# pov.net
KiCad netlist of a schematic drawn in EAGLE
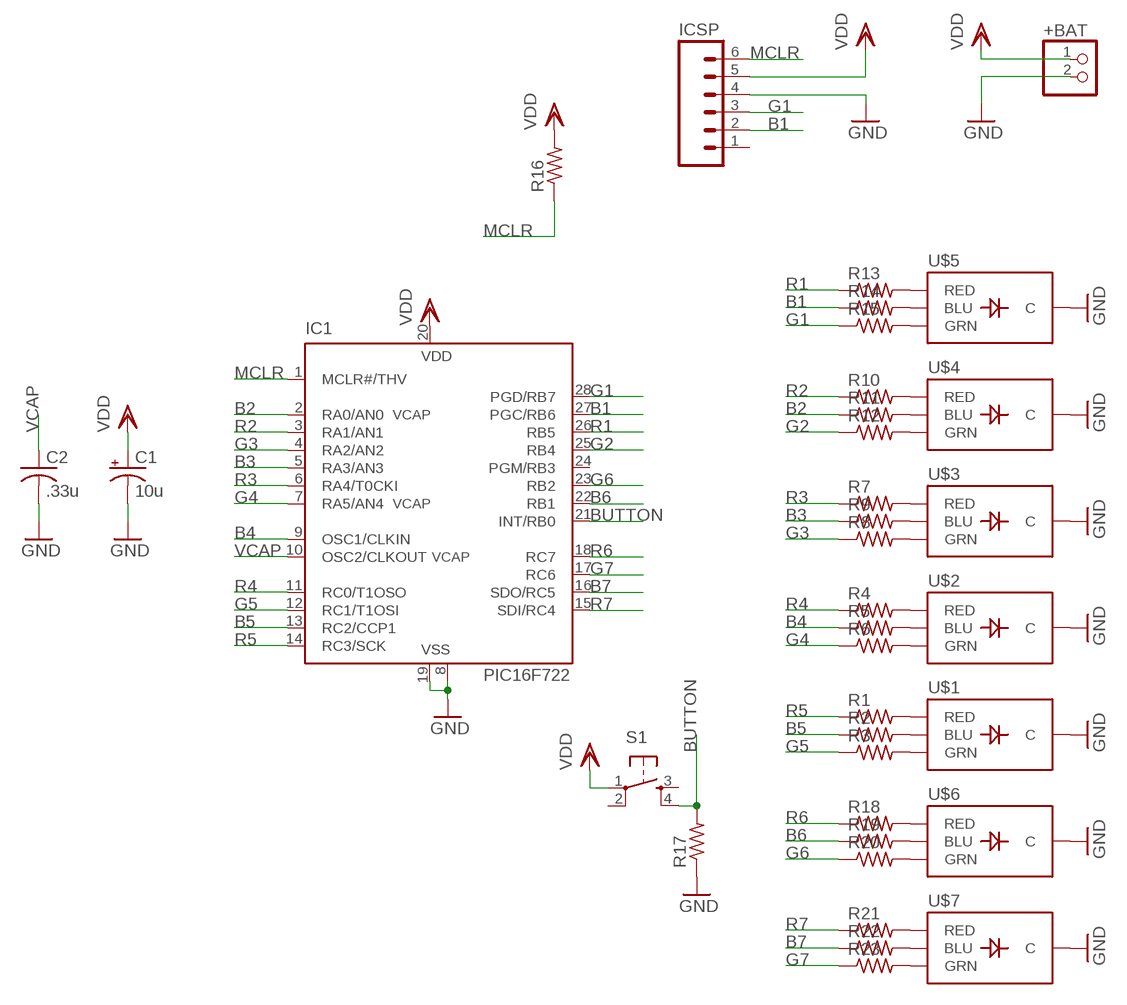
[diagram p0: schematic, sheet 1]

(export (version "E")
  (design (tool "Eeschema 10.0.6"))
  (components
    (comp (ref "+BAT")
      (value "PINHD-1X2")
      (footprint "eagle-import:1X02")
      (libsource (lib "eagle-import") (part "PINHD-1X2"))
    )
    (comp (ref "C1")
      (value "10u")
      (footprint "eagle-import:CPOL-RADIAL-10UF-25V")
      (libsource (lib "eagle-import") (part "CAP_POLPTH2"))
    )
    (comp (ref "C2")
      (value ".33u")
      (footprint "eagle-import:C050-024X044")
      (libsource (lib "eagle-import") (part "C-US050-024X044"))
    )
    (comp (ref "IC1")
      (value "PIC16F722")
      (footprint "eagle-import:DIL28-3")
      (libsource (lib "eagle-import") (part "PIC16872PF"))
    )
    (comp (ref "ICSP")
      (value "M06LOCK")
      (footprint "eagle-import:1X06_LOCK")
      (libsource (lib "eagle-import") (part "M06LOCK"))
    )
    (comp (ref "R1")
      (value "R-US_0207/10")
      (footprint "eagle-import:0207_10")
      (libsource (lib "eagle-import") (part "R-US_0207/10"))
    )
    (comp (ref "R2")
      (value "R-US_0207/10")
      (footprint "eagle-import:0207_10")
      (libsource (lib "eagle-import") (part "R-US_0207/10"))
    )
    (comp (ref "R3")
      (value "R-US_0207/10")
      (footprint "eagle-import:0207_10")
      (libsource (lib "eagle-import") (part "R-US_0207/10"))
    )
    (comp (ref "R4")
      (value "R-US_0207/10")
      (footprint "eagle-import:0207_10")
      (libsource (lib "eagle-import") (part "R-US_0207/10"))
    )
    (comp (ref "R5")
      (value "R-US_0207/10")
      (footprint "eagle-import:0207_10")
      (libsource (lib "eagle-import") (part "R-US_0207/10"))
    )
    (comp (ref "R6")
      (value "R-US_0207/10")
      (footprint "eagle-import:0207_10")
      (libsource (lib "eagle-import") (part "R-US_0207/10"))
    )
    (comp (ref "R7")
      (value "R-US_0207/10")
      (footprint "eagle-import:0207_10")
      (libsource (lib "eagle-import") (part "R-US_0207/10"))
    )
    (comp (ref "R8")
      (value "R-US_0207/10")
      (footprint "eagle-import:0207_10")
      (libsource (lib "eagle-import") (part "R-US_0207/10"))
    )
    (comp (ref "R9")
      (value "R-US_0207/10")
      (footprint "eagle-import:0207_10")
      (libsource (lib "eagle-import") (part "R-US_0207/10"))
    )
    (comp (ref "R10")
      (value "R-US_0207/10")
      (footprint "eagle-import:0207_10")
      (libsource (lib "eagle-import") (part "R-US_0207/10"))
    )
    (comp (ref "R11")
      (value "R-US_0207/10")
      (footprint "eagle-import:0207_10")
      (libsource (lib "eagle-import") (part "R-US_0207/10"))
    )
    (comp (ref "R12")
      (value "R-US_0207/10")
      (footprint "eagle-import:0207_10")
      (libsource (lib "eagle-import") (part "R-US_0207/10"))
    )
    (comp (ref "R13")
      (value "R-US_0207/10")
      (footprint "eagle-import:0207_10")
      (libsource (lib "eagle-import") (part "R-US_0207/10"))
    )
    (comp (ref "R14")
      (value "R-US_0207/10")
      (footprint "eagle-import:0207_10")
      (libsource (lib "eagle-import") (part "R-US_0207/10"))
    )
    (comp (ref "R15")
      (value "R-US_0207/10")
      (footprint "eagle-import:0207_10")
      (libsource (lib "eagle-import") (part "R-US_0207/10"))
    )
    (comp (ref "R16")
      (value "R-US_0207/10")
      (footprint "eagle-import:0207_10")
      (libsource (lib "eagle-import") (part "R-US_0207/10"))
    )
    (comp (ref "R17")
      (value "R-US_0207/10")
      (footprint "eagle-import:0207_10")
      (libsource (lib "eagle-import") (part "R-US_0207/10"))
    )
    (comp (ref "R18")
      (value "R-US_0207/10")
      (footprint "eagle-import:0207_10")
      (libsource (lib "eagle-import") (part "R-US_0207/10"))
    )
    (comp (ref "R19")
      (value "R-US_0207/10")
      (footprint "eagle-import:0207_10")
      (libsource (lib "eagle-import") (part "R-US_0207/10"))
    )
    (comp (ref "R20")
      (value "R-US_0207/10")
      (footprint "eagle-import:0207_10")
      (libsource (lib "eagle-import") (part "R-US_0207/10"))
    )
    (comp (ref "R21")
      (value "R-US_0207/10")
      (footprint "eagle-import:0207_10")
      (libsource (lib "eagle-import") (part "R-US_0207/10"))
    )
    (comp (ref "R22")
      (value "R-US_0207/10")
      (footprint "eagle-import:0207_10")
      (libsource (lib "eagle-import") (part "R-US_0207/10"))
    )
    (comp (ref "R23")
      (value "R-US_0207/10")
      (footprint "eagle-import:0207_10")
      (libsource (lib "eagle-import") (part "R-US_0207/10"))
    )
    (comp (ref "S1")
      (value "TAC_SWITCHPTH")
      (footprint "eagle-import:TACTILE-PTH")
      (libsource (lib "eagle-import") (part "TAC_SWITCHPTH"))
    )
    (comp (ref "U$1")
      (value "LED-TRICOLOR-THROUGHHOLE")
      (footprint "eagle-import:LED-TRICOLOR-THROUGHHOLE")
      (libsource (lib "eagle-import") (part "LED-TRICOLOR-THROUGHHOLE"))
    )
    (comp (ref "U$2")
      (value "LED-TRICOLOR-THROUGHHOLE")
      (footprint "eagle-import:LED-TRICOLOR-THROUGHHOLE")
      (libsource (lib "eagle-import") (part "LED-TRICOLOR-THROUGHHOLE"))
    )
    (comp (ref "U$3")
      (value "LED-TRICOLOR-THROUGHHOLE")
      (footprint "eagle-import:LED-TRICOLOR-THROUGHHOLE")
      (libsource (lib "eagle-import") (part "LED-TRICOLOR-THROUGHHOLE"))
    )
    (comp (ref "U$4")
      (value "LED-TRICOLOR-THROUGHHOLE")
      (footprint "eagle-import:LED-TRICOLOR-THROUGHHOLE")
      (libsource (lib "eagle-import") (part "LED-TRICOLOR-THROUGHHOLE"))
    )
    (comp (ref "U$5")
      (value "LED-TRICOLOR-THROUGHHOLE")
      (footprint "eagle-import:LED-TRICOLOR-THROUGHHOLE")
      (libsource (lib "eagle-import") (part "LED-TRICOLOR-THROUGHHOLE"))
    )
    (comp (ref "U$6")
      (value "LED-TRICOLOR-THROUGHHOLE")
      (footprint "eagle-import:LED-TRICOLOR-THROUGHHOLE")
      (libsource (lib "eagle-import") (part "LED-TRICOLOR-THROUGHHOLE"))
    )
    (comp (ref "U$7")
      (value "LED-TRICOLOR-THROUGHHOLE")
      (footprint "eagle-import:LED-TRICOLOR-THROUGHHOLE")
      (libsource (lib "eagle-import") (part "LED-TRICOLOR-THROUGHHOLE"))
    )
  )
  (nets
    (net (code "1") (name "/B1") (class "Default")
      (node (ref "IC1") (pin "27") (pinfunction "PGC/RB6_27") (pintype "bidirectional"))
      (node (ref "ICSP") (pin "2") (pinfunction "2_2") (pintype "passive"))
      (node (ref "R14") (pin "1") (pinfunction "1_1") (pintype "passive"))
    )
    (net (code "2") (name "/B2") (class "Default")
      (node (ref "IC1") (pin "2") (pinfunction "RA0/AN0_2") (pintype "bidirectional"))
      (node (ref "R11") (pin "1") (pinfunction "1_1") (pintype "passive"))
    )
    (net (code "3") (name "/B3") (class "Default")
      (node (ref "IC1") (pin "5") (pinfunction "RA3/AN3_5") (pintype "bidirectional"))
      (node (ref "R9") (pin "1") (pinfunction "1_1") (pintype "passive"))
    )
    (net (code "4") (name "/B4") (class "Default")
      (node (ref "IC1") (pin "9") (pinfunction "OSC1/CLKIN_9") (pintype "input"))
      (node (ref "R5") (pin "1") (pinfunction "1_1") (pintype "passive"))
    )
    (net (code "5") (name "/B5") (class "Default")
      (node (ref "IC1") (pin "13") (pinfunction "RC2/CCP1_13") (pintype "bidirectional"))
      (node (ref "R2") (pin "1") (pinfunction "1_1") (pintype "passive"))
    )
    (net (code "6") (name "/B6") (class "Default")
      (node (ref "IC1") (pin "22") (pinfunction "RB1_22") (pintype "bidirectional"))
      (node (ref "R19") (pin "1") (pinfunction "1_1") (pintype "passive"))
    )
    (net (code "7") (name "/B7") (class "Default")
      (node (ref "IC1") (pin "16") (pinfunction "SDO/RC5_16") (pintype "bidirectional"))
      (node (ref "R22") (pin "1") (pinfunction "1_1") (pintype "passive"))
    )
    (net (code "8") (name "/BUTTON") (class "Default")
      (node (ref "IC1") (pin "21") (pinfunction "INT/RB0_21") (pintype "bidirectional"))
      (node (ref "R17") (pin "2") (pinfunction "2_2") (pintype "passive"))
      (node (ref "S1") (pin "4") (pinfunction "4_4") (pintype "passive"))
    )
    (net (code "9") (name "/G1") (class "Default")
      (node (ref "IC1") (pin "28") (pinfunction "PGD/RB7_28") (pintype "bidirectional"))
      (node (ref "ICSP") (pin "3") (pinfunction "3_3") (pintype "passive"))
      (node (ref "R15") (pin "1") (pinfunction "1_1") (pintype "passive"))
    )
    (net (code "10") (name "/G2") (class "Default")
      (node (ref "IC1") (pin "25") (pinfunction "RB4_25") (pintype "bidirectional"))
      (node (ref "R12") (pin "1") (pinfunction "1_1") (pintype "passive"))
    )
    (net (code "11") (name "/G3") (class "Default")
      (node (ref "IC1") (pin "4") (pinfunction "RA2/AN2_4") (pintype "bidirectional"))
      (node (ref "R8") (pin "1") (pinfunction "1_1") (pintype "passive"))
    )
    (net (code "12") (name "/G4") (class "Default")
      (node (ref "IC1") (pin "7") (pinfunction "RA5/AN4_7") (pintype "bidirectional"))
      (node (ref "R6") (pin "1") (pinfunction "1_1") (pintype "passive"))
    )
    (net (code "13") (name "/G5") (class "Default")
      (node (ref "IC1") (pin "12") (pinfunction "RC1/T1OSI_12") (pintype "bidirectional"))
      (node (ref "R3") (pin "1") (pinfunction "1_1") (pintype "passive"))
    )
    (net (code "14") (name "/G6") (class "Default")
      (node (ref "IC1") (pin "23") (pinfunction "RB2_23") (pintype "bidirectional"))
      (node (ref "R20") (pin "1") (pinfunction "1_1") (pintype "passive"))
    )
    (net (code "15") (name "/G7") (class "Default")
      (node (ref "IC1") (pin "17") (pinfunction "RC6_17") (pintype "bidirectional"))
      (node (ref "R23") (pin "1") (pinfunction "1_1") (pintype "passive"))
    )
    (net (code "16") (name "/MCLR") (class "Default")
      (node (ref "IC1") (pin "1") (pinfunction "MCLR#/THV_1") (pintype "input"))
      (node (ref "ICSP") (pin "6") (pinfunction "6_6") (pintype "passive"))
      (node (ref "R16") (pin "1") (pinfunction "1_1") (pintype "passive"))
    )
    (net (code "17") (name "/R1") (class "Default")
      (node (ref "IC1") (pin "26") (pinfunction "RB5_26") (pintype "bidirectional"))
      (node (ref "R13") (pin "1") (pinfunction "1_1") (pintype "passive"))
    )
    (net (code "18") (name "/R2") (class "Default")
      (node (ref "IC1") (pin "3") (pinfunction "RA1/AN1_3") (pintype "bidirectional"))
      (node (ref "R10") (pin "1") (pinfunction "1_1") (pintype "passive"))
    )
    (net (code "19") (name "/R3") (class "Default")
      (node (ref "IC1") (pin "6") (pinfunction "RA4/T0CKI_6") (pintype "bidirectional"))
      (node (ref "R7") (pin "1") (pinfunction "1_1") (pintype "passive"))
    )
    (net (code "20") (name "/R4") (class "Default")
      (node (ref "IC1") (pin "11") (pinfunction "RC0/T1OSO_11") (pintype "bidirectional"))
      (node (ref "R4") (pin "1") (pinfunction "1_1") (pintype "passive"))
    )
    (net (code "21") (name "/R5") (class "Default")
      (node (ref "IC1") (pin "14") (pinfunction "RC3/SCK_14") (pintype "bidirectional"))
      (node (ref "R1") (pin "1") (pinfunction "1_1") (pintype "passive"))
    )
    (net (code "22") (name "/R6") (class "Default")
      (node (ref "IC1") (pin "18") (pinfunction "RC7_18") (pintype "bidirectional"))
      (node (ref "R18") (pin "1") (pinfunction "1_1") (pintype "passive"))
    )
    (net (code "23") (name "/R7") (class "Default")
      (node (ref "IC1") (pin "15") (pinfunction "SDI/RC4_15") (pintype "bidirectional"))
      (node (ref "R21") (pin "1") (pinfunction "1_1") (pintype "passive"))
    )
    (net (code "24") (name "/VCAP") (class "Default")
      (node (ref "C2") (pin "1") (pinfunction "1_1") (pintype "passive"))
      (node (ref "IC1") (pin "10") (pinfunction "OSC2/CLKOUT_10") (pintype "output"))
    )
    (net (code "25") (name "GND") (class "Default")
      (node (ref "+BAT") (pin "2") (pinfunction "2_2") (pintype "passive"))
      (node (ref "C1") (pin "2") (pinfunction "-_2") (pintype "passive"))
      (node (ref "C2") (pin "2") (pinfunction "2_2") (pintype "passive"))
      (node (ref "IC1") (pin "19") (pinfunction "VSS_19") (pintype "power_in"))
      (node (ref "IC1") (pin "8") (pinfunction "VSS_8") (pintype "power_in"))
      (node (ref "ICSP") (pin "4") (pinfunction "4_4") (pintype "passive"))
      (node (ref "R17") (pin "1") (pinfunction "1_1") (pintype "passive"))
      (node (ref "U$1") (pin "GND") (pinfunction "C_GND") (pintype "bidirectional"))
      (node (ref "U$2") (pin "GND") (pinfunction "C_GND") (pintype "bidirectional"))
      (node (ref "U$3") (pin "GND") (pinfunction "C_GND") (pintype "bidirectional"))
      (node (ref "U$4") (pin "GND") (pinfunction "C_GND") (pintype "bidirectional"))
      (node (ref "U$5") (pin "GND") (pinfunction "C_GND") (pintype "bidirectional"))
      (node (ref "U$6") (pin "GND") (pinfunction "C_GND") (pintype "bidirectional"))
      (node (ref "U$7") (pin "GND") (pinfunction "C_GND") (pintype "bidirectional"))
    )
    (net (code "26") (name "Net-(R1-Pad2)") (class "Default")
      (node (ref "R1") (pin "2") (pinfunction "2_2") (pintype "passive"))
      (node (ref "U$1") (pin "RED") (pinfunction "RED_RED") (pintype "bidirectional"))
    )
    (net (code "27") (name "Net-(R2-Pad2)") (class "Default")
      (node (ref "R2") (pin "2") (pinfunction "2_2") (pintype "passive"))
      (node (ref "U$1") (pin "BLU") (pinfunction "BLU_BLU") (pintype "bidirectional"))
    )
    (net (code "28") (name "Net-(R3-Pad2)") (class "Default")
      (node (ref "R3") (pin "2") (pinfunction "2_2") (pintype "passive"))
      (node (ref "U$1") (pin "GRN") (pinfunction "GRN_GRN") (pintype "bidirectional"))
    )
    (net (code "29") (name "Net-(R4-Pad2)") (class "Default")
      (node (ref "R4") (pin "2") (pinfunction "2_2") (pintype "passive"))
      (node (ref "U$2") (pin "RED") (pinfunction "RED_RED") (pintype "bidirectional"))
    )
    (net (code "30") (name "Net-(R5-Pad2)") (class "Default")
      (node (ref "R5") (pin "2") (pinfunction "2_2") (pintype "passive"))
      (node (ref "U$2") (pin "BLU") (pinfunction "BLU_BLU") (pintype "bidirectional"))
    )
    (net (code "31") (name "Net-(R6-Pad2)") (class "Default")
      (node (ref "R6") (pin "2") (pinfunction "2_2") (pintype "passive"))
      (node (ref "U$2") (pin "GRN") (pinfunction "GRN_GRN") (pintype "bidirectional"))
    )
    (net (code "32") (name "Net-(R7-Pad2)") (class "Default")
      (node (ref "R7") (pin "2") (pinfunction "2_2") (pintype "passive"))
      (node (ref "U$3") (pin "RED") (pinfunction "RED_RED") (pintype "bidirectional"))
    )
    (net (code "33") (name "Net-(R8-Pad2)") (class "Default")
      (node (ref "R8") (pin "2") (pinfunction "2_2") (pintype "passive"))
      (node (ref "U$3") (pin "GRN") (pinfunction "GRN_GRN") (pintype "bidirectional"))
    )
    (net (code "34") (name "Net-(R9-Pad2)") (class "Default")
      (node (ref "R9") (pin "2") (pinfunction "2_2") (pintype "passive"))
      (node (ref "U$3") (pin "BLU") (pinfunction "BLU_BLU") (pintype "bidirectional"))
    )
    (net (code "35") (name "Net-(R10-Pad2)") (class "Default")
      (node (ref "R10") (pin "2") (pinfunction "2_2") (pintype "passive"))
      (node (ref "U$4") (pin "RED") (pinfunction "RED_RED") (pintype "bidirectional"))
    )
    (net (code "36") (name "Net-(R11-Pad2)") (class "Default")
      (node (ref "R11") (pin "2") (pinfunction "2_2") (pintype "passive"))
      (node (ref "U$4") (pin "BLU") (pinfunction "BLU_BLU") (pintype "bidirectional"))
    )
    (net (code "37") (name "Net-(R12-Pad2)") (class "Default")
      (node (ref "R12") (pin "2") (pinfunction "2_2") (pintype "passive"))
      (node (ref "U$4") (pin "GRN") (pinfunction "GRN_GRN") (pintype "bidirectional"))
    )
    (net (code "38") (name "Net-(R13-Pad2)") (class "Default")
      (node (ref "R13") (pin "2") (pinfunction "2_2") (pintype "passive"))
      (node (ref "U$5") (pin "RED") (pinfunction "RED_RED") (pintype "bidirectional"))
    )
    (net (code "39") (name "Net-(R14-Pad2)") (class "Default")
      (node (ref "R14") (pin "2") (pinfunction "2_2") (pintype "passive"))
      (node (ref "U$5") (pin "BLU") (pinfunction "BLU_BLU") (pintype "bidirectional"))
    )
    (net (code "40") (name "Net-(R15-Pad2)") (class "Default")
      (node (ref "R15") (pin "2") (pinfunction "2_2") (pintype "passive"))
      (node (ref "U$5") (pin "GRN") (pinfunction "GRN_GRN") (pintype "bidirectional"))
    )
    (net (code "41") (name "Net-(R18-Pad2)") (class "Default")
      (node (ref "R18") (pin "2") (pinfunction "2_2") (pintype "passive"))
      (node (ref "U$6") (pin "RED") (pinfunction "RED_RED") (pintype "bidirectional"))
    )
    (net (code "42") (name "Net-(R19-Pad2)") (class "Default")
      (node (ref "R19") (pin "2") (pinfunction "2_2") (pintype "passive"))
      (node (ref "U$6") (pin "BLU") (pinfunction "BLU_BLU") (pintype "bidirectional"))
    )
    (net (code "43") (name "Net-(R20-Pad2)") (class "Default")
      (node (ref "R20") (pin "2") (pinfunction "2_2") (pintype "passive"))
      (node (ref "U$6") (pin "GRN") (pinfunction "GRN_GRN") (pintype "bidirectional"))
    )
    (net (code "44") (name "Net-(R21-Pad2)") (class "Default")
      (node (ref "R21") (pin "2") (pinfunction "2_2") (pintype "passive"))
      (node (ref "U$7") (pin "RED") (pinfunction "RED_RED") (pintype "bidirectional"))
    )
    (net (code "45") (name "Net-(R22-Pad2)") (class "Default")
      (node (ref "R22") (pin "2") (pinfunction "2_2") (pintype "passive"))
      (node (ref "U$7") (pin "BLU") (pinfunction "BLU_BLU") (pintype "bidirectional"))
    )
    (net (code "46") (name "Net-(R23-Pad2)") (class "Default")
      (node (ref "R23") (pin "2") (pinfunction "2_2") (pintype "passive"))
      (node (ref "U$7") (pin "GRN") (pinfunction "GRN_GRN") (pintype "bidirectional"))
    )
    (net (code "47") (name "VDD") (class "Default")
      (node (ref "+BAT") (pin "1") (pinfunction "1_1") (pintype "passive"))
      (node (ref "C1") (pin "1") (pinfunction "+_1") (pintype "passive"))
      (node (ref "IC1") (pin "20") (pinfunction "VDD_20") (pintype "power_in"))
      (node (ref "ICSP") (pin "5") (pinfunction "5_5") (pintype "passive"))
      (node (ref "R16") (pin "2") (pinfunction "2_2") (pintype "passive"))
      (node (ref "S1") (pin "1") (pinfunction "1_1") (pintype "passive"))
    )
    (net (code "48") (name "unconnected-(IC1-PGM{slash}RB3-Pad24)") (class "Default")
      (node (ref "IC1") (pin "24") (pinfunction "PGM/RB3_24") (pintype "bidirectional"))
    )
    (net (code "49") (name "unconnected-(ICSP-Pad1)") (class "Default")
      (node (ref "ICSP") (pin "1") (pinfunction "1_1") (pintype "passive"))
    )
    (net (code "50") (name "unconnected-(S1-Pad2)") (class "Default")
      (node (ref "S1") (pin "2") (pinfunction "2_2") (pintype "passive"))
    )
    (net (code "51") (name "unconnected-(S1-Pad3)") (class "Default")
      (node (ref "S1") (pin "3") (pinfunction "3_3") (pintype "passive"))
    )
  )
)
